# BUZZER.net
KiCad netlist of a schematic drawn in Altium Designer
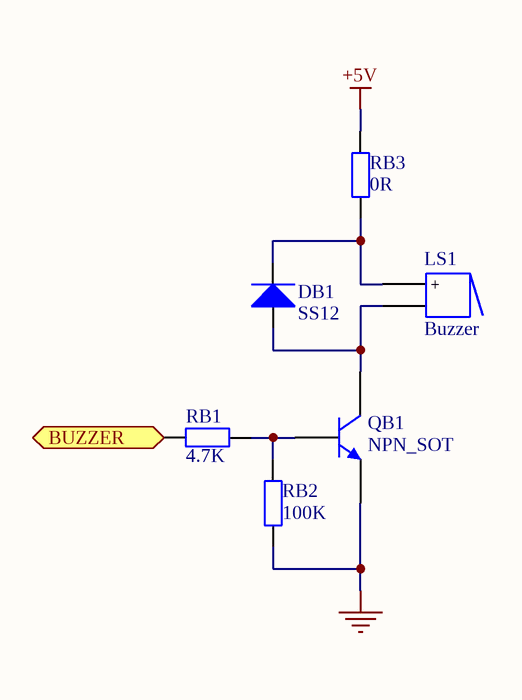
[diagram p0: BUZZER.SchDoc]

(export (version "E")
  (design (tool "Eeschema 10.0.6"))
  (components
    (comp (ref "DB1")
      (value "Diode")
      (footprint "DO-214AC")
      (fields (field (name "SMA") "SS12"))
      (libsource (lib "Peace的集成库") (part "Diode"))
    )
    (comp (ref "LS1")
      (value "Buzzer")
      (footprint "Buzzer 5")
      (description "Magnetic Transducer Buzzer")
      (fields (field (name "PUBLISHER") "Altium Limited"))
      (libsource (lib "Peace的集成库") (part "Buzzer"))
    )
    (comp (ref "QB1")
      (value "NPN_SOT")
      (footprint "SOT23_N")
      (description "NPN Bipolar Transistor")
      (fields (field (name "PUBLISHER") "Altium Limited"))
      (libsource (lib "Peace的集成库") (part "NPN_SOT"))
    )
    (comp (ref "RB1")
      (value "4.7K")
      (footprint "RESC1608N")
      (description "Resistor")
      (fields (field (name "Comment") "Res1") (field (name "PUBLISHER") "Altium Limited"))
      (libsource (lib "") (part "Res1_1"))
    )
    (comp (ref "RB2")
      (value "100K")
      (footprint "RESC1608N")
      (description "Resistor")
      (fields (field (name "Comment") "Res1") (field (name "PUBLISHER") "Altium Limited"))
      (libsource (lib "") (part "Res1_2"))
    )
    (comp (ref "RB3")
      (value "0R")
      (footprint "RESC1608N")
      (description "Resistor")
      (fields (field (name "Comment") "Res1") (field (name "PUBLISHER") "Altium Limited"))
      (libsource (lib "Peace的集成库") (part "Res1"))
    )
  )
  (nets
    (net (code "1") (name "+5V") (class "Default")
      (node (ref "RB3") (pin "2") (pinfunction "2_2") (pintype "passive"))
    )
    (net (code "2") (name "/BUZZER") (class "Default")
      (node (ref "RB1") (pin "2") (pinfunction "2_2") (pintype "passive"))
    )
    (net (code "3") (name "GND") (class "Default")
      (node (ref "QB1") (pin "2") (pinfunction "E_2") (pintype "passive"))
      (node (ref "RB2") (pin "2") (pinfunction "2_2") (pintype "passive"))
    )
    (net (code "4") (name "Net-(DB1-A)") (class "Default")
      (node (ref "DB1") (pin "1") (pinfunction "A_1") (pintype "passive"))
      (node (ref "LS1") (pin "2") (pinfunction "2_2") (pintype "passive"))
      (node (ref "QB1") (pin "1") (pinfunction "C_1") (pintype "passive"))
    )
    (net (code "5") (name "Net-(DB1-K)") (class "Default")
      (node (ref "DB1") (pin "2") (pinfunction "K_2") (pintype "passive"))
      (node (ref "LS1") (pin "1") (pinfunction "+_1") (pintype "passive"))
      (node (ref "RB3") (pin "1") (pinfunction "1_1") (pintype "passive"))
    )
    (net (code "6") (name "Net-(QB1-B)") (class "Default")
      (node (ref "QB1") (pin "3") (pinfunction "B_3") (pintype "passive"))
      (node (ref "RB1") (pin "1") (pinfunction "1_1") (pintype "passive"))
      (node (ref "RB2") (pin "1") (pinfunction "1_1") (pintype "passive"))
    )
  )
)
